# dev-test-proto.net
KiCad netlist of a schematic drawn in EAGLE
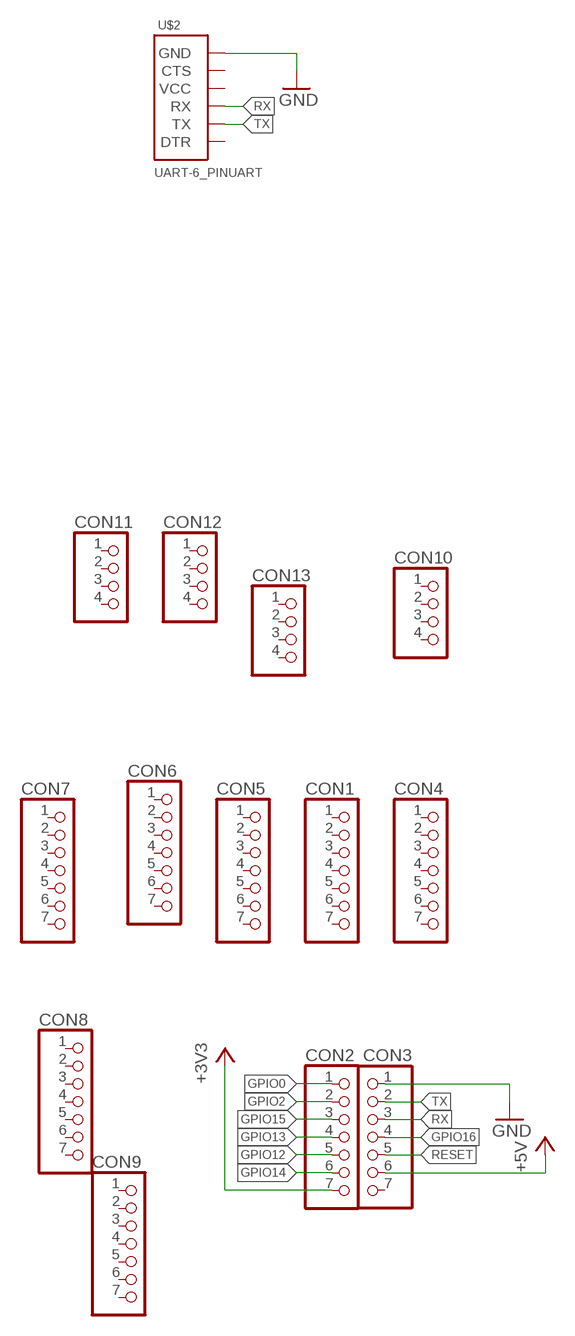
[diagram p0: schematic, sheet 1]

(export (version "E")
  (design (tool "Eeschema 10.0.6"))
  (components
    (comp (ref "CON1")
      (value "GENERIC-1X7THT")
      (footprint "eagle-import:PINHEADER-100MIL-1X7")
      (libsource (lib "eagle-import") (part "GENERIC-1X7THT"))
    )
    (comp (ref "CON2")
      (value "GENERIC-1X7THT")
      (footprint "eagle-import:PINHEADER-100MIL-1X7")
      (libsource (lib "eagle-import") (part "GENERIC-1X7THT"))
    )
    (comp (ref "CON3")
      (value "GENERIC-1X7THT")
      (footprint "eagle-import:PINHEADER-100MIL-1X7")
      (libsource (lib "eagle-import") (part "GENERIC-1X7THT"))
    )
    (comp (ref "CON4")
      (value "GENERIC-1X7THT")
      (footprint "eagle-import:PINHEADER-100MIL-1X7")
      (libsource (lib "eagle-import") (part "GENERIC-1X7THT"))
    )
    (comp (ref "CON5")
      (value "GENERIC-1X7THT")
      (footprint "eagle-import:PINHEADER-100MIL-1X7")
      (libsource (lib "eagle-import") (part "GENERIC-1X7THT"))
    )
    (comp (ref "CON6")
      (value "GENERIC-1X7THT")
      (footprint "eagle-import:PINHEADER-100MIL-1X7")
      (libsource (lib "eagle-import") (part "GENERIC-1X7THT"))
    )
    (comp (ref "CON7")
      (value "GENERIC-1X7THT")
      (footprint "eagle-import:PINHEADER-100MIL-1X7")
      (libsource (lib "eagle-import") (part "GENERIC-1X7THT"))
    )
    (comp (ref "CON8")
      (value "GENERIC-1X7THT")
      (footprint "eagle-import:PINHEADER-100MIL-1X7")
      (libsource (lib "eagle-import") (part "GENERIC-1X7THT"))
    )
    (comp (ref "CON9")
      (value "GENERIC-1X7THT")
      (footprint "eagle-import:PINHEADER-100MIL-1X7")
      (libsource (lib "eagle-import") (part "GENERIC-1X7THT"))
    )
    (comp (ref "CON10")
      (value "GENERIC-1X4STRAIGHT")
      (footprint "eagle-import:PINHEADER-100MIL-1X4-NOSILK")
      (libsource (lib "eagle-import") (part "GENERIC-1X4STRAIGHT"))
    )
    (comp (ref "CON11")
      (value "GENERIC-1X4STRAIGHT")
      (footprint "eagle-import:PINHEADER-100MIL-1X4-NOSILK")
      (libsource (lib "eagle-import") (part "GENERIC-1X4STRAIGHT"))
    )
    (comp (ref "CON12")
      (value "GENERIC-1X4STRAIGHT")
      (footprint "eagle-import:PINHEADER-100MIL-1X4-NOSILK")
      (libsource (lib "eagle-import") (part "GENERIC-1X4STRAIGHT"))
    )
    (comp (ref "CON13")
      (value "GENERIC-1X4STRAIGHT")
      (footprint "eagle-import:PINHEADER-100MIL-1X4-NOSILK")
      (libsource (lib "eagle-import") (part "GENERIC-1X4STRAIGHT"))
    )
    (comp (ref "U$2")
      (value "UART-6_PINUART")
      (footprint "eagle-import:ANGLE-1X6")
      (libsource (lib "eagle-import") (part "UART-6_PINUART"))
    )
  )
  (nets
    (net (code "1") (name "+3V3") (class "Default")
      (node (ref "CON2") (pin "7") (pinfunction "7_7") (pintype "passive"))
    )
    (net (code "2") (name "+5V") (class "Default")
      (node (ref "CON3") (pin "6") (pinfunction "6_6") (pintype "passive"))
    )
    (net (code "3") (name "GND") (class "Default")
      (node (ref "CON3") (pin "1") (pinfunction "1_1") (pintype "passive"))
      (node (ref "U$2") (pin "1") (pinfunction "GND_1") (pintype "bidirectional"))
    )
    (net (code "4") (name "GPIO0") (class "Default")
      (node (ref "CON2") (pin "1") (pinfunction "1_1") (pintype "passive"))
    )
    (net (code "5") (name "GPIO2") (class "Default")
      (node (ref "CON2") (pin "2") (pinfunction "2_2") (pintype "passive"))
    )
    (net (code "6") (name "GPIO12") (class "Default")
      (node (ref "CON2") (pin "5") (pinfunction "5_5") (pintype "passive"))
    )
    (net (code "7") (name "GPIO13") (class "Default")
      (node (ref "CON2") (pin "4") (pinfunction "4_4") (pintype "passive"))
    )
    (net (code "8") (name "GPIO14") (class "Default")
      (node (ref "CON2") (pin "6") (pinfunction "6_6") (pintype "passive"))
    )
    (net (code "9") (name "GPIO15") (class "Default")
      (node (ref "CON2") (pin "3") (pinfunction "3_3") (pintype "passive"))
    )
    (net (code "10") (name "GPIO16") (class "Default")
      (node (ref "CON3") (pin "4") (pinfunction "4_4") (pintype "passive"))
    )
    (net (code "11") (name "RESET") (class "Default")
      (node (ref "CON3") (pin "5") (pinfunction "5_5") (pintype "passive"))
    )
    (net (code "12") (name "RX") (class "Default")
      (node (ref "CON3") (pin "3") (pinfunction "3_3") (pintype "passive"))
      (node (ref "U$2") (pin "4") (pinfunction "RX_4") (pintype "bidirectional"))
    )
    (net (code "13") (name "TX") (class "Default")
      (node (ref "CON3") (pin "2") (pinfunction "2_2") (pintype "passive"))
      (node (ref "U$2") (pin "5") (pinfunction "TX_5") (pintype "bidirectional"))
    )
    (net (code "14") (name "unconnected-(CON1-Pad1)") (class "Default")
      (node (ref "CON1") (pin "1") (pinfunction "1_1") (pintype "passive"))
    )
    (net (code "15") (name "unconnected-(CON1-Pad2)") (class "Default")
      (node (ref "CON1") (pin "2") (pinfunction "2_2") (pintype "passive"))
    )
    (net (code "16") (name "unconnected-(CON1-Pad3)") (class "Default")
      (node (ref "CON1") (pin "3") (pinfunction "3_3") (pintype "passive"))
    )
    (net (code "17") (name "unconnected-(CON1-Pad4)") (class "Default")
      (node (ref "CON1") (pin "4") (pinfunction "4_4") (pintype "passive"))
    )
    (net (code "18") (name "unconnected-(CON1-Pad5)") (class "Default")
      (node (ref "CON1") (pin "5") (pinfunction "5_5") (pintype "passive"))
    )
    (net (code "19") (name "unconnected-(CON1-Pad6)") (class "Default")
      (node (ref "CON1") (pin "6") (pinfunction "6_6") (pintype "passive"))
    )
    (net (code "20") (name "unconnected-(CON1-Pad7)") (class "Default")
      (node (ref "CON1") (pin "7") (pinfunction "7_7") (pintype "passive"))
    )
    (net (code "21") (name "unconnected-(CON3-Pad7)") (class "Default")
      (node (ref "CON3") (pin "7") (pinfunction "7_7") (pintype "passive"))
    )
    (net (code "22") (name "unconnected-(CON4-Pad1)") (class "Default")
      (node (ref "CON4") (pin "1") (pinfunction "1_1") (pintype "passive"))
    )
    (net (code "23") (name "unconnected-(CON4-Pad2)") (class "Default")
      (node (ref "CON4") (pin "2") (pinfunction "2_2") (pintype "passive"))
    )
    (net (code "24") (name "unconnected-(CON4-Pad3)") (class "Default")
      (node (ref "CON4") (pin "3") (pinfunction "3_3") (pintype "passive"))
    )
    (net (code "25") (name "unconnected-(CON4-Pad4)") (class "Default")
      (node (ref "CON4") (pin "4") (pinfunction "4_4") (pintype "passive"))
    )
    (net (code "26") (name "unconnected-(CON4-Pad5)") (class "Default")
      (node (ref "CON4") (pin "5") (pinfunction "5_5") (pintype "passive"))
    )
    (net (code "27") (name "unconnected-(CON4-Pad6)") (class "Default")
      (node (ref "CON4") (pin "6") (pinfunction "6_6") (pintype "passive"))
    )
    (net (code "28") (name "unconnected-(CON4-Pad7)") (class "Default")
      (node (ref "CON4") (pin "7") (pinfunction "7_7") (pintype "passive"))
    )
    (net (code "29") (name "unconnected-(CON5-Pad1)") (class "Default")
      (node (ref "CON5") (pin "1") (pinfunction "1_1") (pintype "passive"))
    )
    (net (code "30") (name "unconnected-(CON5-Pad2)") (class "Default")
      (node (ref "CON5") (pin "2") (pinfunction "2_2") (pintype "passive"))
    )
    (net (code "31") (name "unconnected-(CON5-Pad3)") (class "Default")
      (node (ref "CON5") (pin "3") (pinfunction "3_3") (pintype "passive"))
    )
    (net (code "32") (name "unconnected-(CON5-Pad4)") (class "Default")
      (node (ref "CON5") (pin "4") (pinfunction "4_4") (pintype "passive"))
    )
    (net (code "33") (name "unconnected-(CON5-Pad5)") (class "Default")
      (node (ref "CON5") (pin "5") (pinfunction "5_5") (pintype "passive"))
    )
    (net (code "34") (name "unconnected-(CON5-Pad6)") (class "Default")
      (node (ref "CON5") (pin "6") (pinfunction "6_6") (pintype "passive"))
    )
    (net (code "35") (name "unconnected-(CON5-Pad7)") (class "Default")
      (node (ref "CON5") (pin "7") (pinfunction "7_7") (pintype "passive"))
    )
    (net (code "36") (name "unconnected-(CON6-Pad1)") (class "Default")
      (node (ref "CON6") (pin "1") (pinfunction "1_1") (pintype "passive"))
    )
    (net (code "37") (name "unconnected-(CON6-Pad2)") (class "Default")
      (node (ref "CON6") (pin "2") (pinfunction "2_2") (pintype "passive"))
    )
    (net (code "38") (name "unconnected-(CON6-Pad3)") (class "Default")
      (node (ref "CON6") (pin "3") (pinfunction "3_3") (pintype "passive"))
    )
    (net (code "39") (name "unconnected-(CON6-Pad4)") (class "Default")
      (node (ref "CON6") (pin "4") (pinfunction "4_4") (pintype "passive"))
    )
    (net (code "40") (name "unconnected-(CON6-Pad5)") (class "Default")
      (node (ref "CON6") (pin "5") (pinfunction "5_5") (pintype "passive"))
    )
    (net (code "41") (name "unconnected-(CON6-Pad6)") (class "Default")
      (node (ref "CON6") (pin "6") (pinfunction "6_6") (pintype "passive"))
    )
    (net (code "42") (name "unconnected-(CON6-Pad7)") (class "Default")
      (node (ref "CON6") (pin "7") (pinfunction "7_7") (pintype "passive"))
    )
    (net (code "43") (name "unconnected-(CON7-Pad1)") (class "Default")
      (node (ref "CON7") (pin "1") (pinfunction "1_1") (pintype "passive"))
    )
    (net (code "44") (name "unconnected-(CON7-Pad2)") (class "Default")
      (node (ref "CON7") (pin "2") (pinfunction "2_2") (pintype "passive"))
    )
    (net (code "45") (name "unconnected-(CON7-Pad3)") (class "Default")
      (node (ref "CON7") (pin "3") (pinfunction "3_3") (pintype "passive"))
    )
    (net (code "46") (name "unconnected-(CON7-Pad4)") (class "Default")
      (node (ref "CON7") (pin "4") (pinfunction "4_4") (pintype "passive"))
    )
    (net (code "47") (name "unconnected-(CON7-Pad5)") (class "Default")
      (node (ref "CON7") (pin "5") (pinfunction "5_5") (pintype "passive"))
    )
    (net (code "48") (name "unconnected-(CON7-Pad6)") (class "Default")
      (node (ref "CON7") (pin "6") (pinfunction "6_6") (pintype "passive"))
    )
    (net (code "49") (name "unconnected-(CON7-Pad7)") (class "Default")
      (node (ref "CON7") (pin "7") (pinfunction "7_7") (pintype "passive"))
    )
    (net (code "50") (name "unconnected-(CON8-Pad1)") (class "Default")
      (node (ref "CON8") (pin "1") (pinfunction "1_1") (pintype "passive"))
    )
    (net (code "51") (name "unconnected-(CON8-Pad2)") (class "Default")
      (node (ref "CON8") (pin "2") (pinfunction "2_2") (pintype "passive"))
    )
    (net (code "52") (name "unconnected-(CON8-Pad3)") (class "Default")
      (node (ref "CON8") (pin "3") (pinfunction "3_3") (pintype "passive"))
    )
    (net (code "53") (name "unconnected-(CON8-Pad4)") (class "Default")
      (node (ref "CON8") (pin "4") (pinfunction "4_4") (pintype "passive"))
    )
    (net (code "54") (name "unconnected-(CON8-Pad5)") (class "Default")
      (node (ref "CON8") (pin "5") (pinfunction "5_5") (pintype "passive"))
    )
    (net (code "55") (name "unconnected-(CON8-Pad6)") (class "Default")
      (node (ref "CON8") (pin "6") (pinfunction "6_6") (pintype "passive"))
    )
    (net (code "56") (name "unconnected-(CON8-Pad7)") (class "Default")
      (node (ref "CON8") (pin "7") (pinfunction "7_7") (pintype "passive"))
    )
    (net (code "57") (name "unconnected-(CON9-Pad1)") (class "Default")
      (node (ref "CON9") (pin "1") (pinfunction "1_1") (pintype "passive"))
    )
    (net (code "58") (name "unconnected-(CON9-Pad2)") (class "Default")
      (node (ref "CON9") (pin "2") (pinfunction "2_2") (pintype "passive"))
    )
    (net (code "59") (name "unconnected-(CON9-Pad3)") (class "Default")
      (node (ref "CON9") (pin "3") (pinfunction "3_3") (pintype "passive"))
    )
    (net (code "60") (name "unconnected-(CON9-Pad4)") (class "Default")
      (node (ref "CON9") (pin "4") (pinfunction "4_4") (pintype "passive"))
    )
    (net (code "61") (name "unconnected-(CON9-Pad5)") (class "Default")
      (node (ref "CON9") (pin "5") (pinfunction "5_5") (pintype "passive"))
    )
    (net (code "62") (name "unconnected-(CON9-Pad6)") (class "Default")
      (node (ref "CON9") (pin "6") (pinfunction "6_6") (pintype "passive"))
    )
    (net (code "63") (name "unconnected-(CON9-Pad7)") (class "Default")
      (node (ref "CON9") (pin "7") (pinfunction "7_7") (pintype "passive"))
    )
    (net (code "64") (name "unconnected-(CON10-Pad1)") (class "Default")
      (node (ref "CON10") (pin "1") (pinfunction "1_1") (pintype "passive"))
    )
    (net (code "65") (name "unconnected-(CON10-Pad2)") (class "Default")
      (node (ref "CON10") (pin "2") (pinfunction "2_2") (pintype "passive"))
    )
    (net (code "66") (name "unconnected-(CON10-Pad3)") (class "Default")
      (node (ref "CON10") (pin "3") (pinfunction "3_3") (pintype "passive"))
    )
    (net (code "67") (name "unconnected-(CON10-Pad4)") (class "Default")
      (node (ref "CON10") (pin "4") (pinfunction "4_4") (pintype "passive"))
    )
    (net (code "68") (name "unconnected-(CON11-Pad1)") (class "Default")
      (node (ref "CON11") (pin "1") (pinfunction "1_1") (pintype "passive"))
    )
    (net (code "69") (name "unconnected-(CON11-Pad2)") (class "Default")
      (node (ref "CON11") (pin "2") (pinfunction "2_2") (pintype "passive"))
    )
    (net (code "70") (name "unconnected-(CON11-Pad3)") (class "Default")
      (node (ref "CON11") (pin "3") (pinfunction "3_3") (pintype "passive"))
    )
    (net (code "71") (name "unconnected-(CON11-Pad4)") (class "Default")
      (node (ref "CON11") (pin "4") (pinfunction "4_4") (pintype "passive"))
    )
    (net (code "72") (name "unconnected-(CON12-Pad1)") (class "Default")
      (node (ref "CON12") (pin "1") (pinfunction "1_1") (pintype "passive"))
    )
    (net (code "73") (name "unconnected-(CON12-Pad2)") (class "Default")
      (node (ref "CON12") (pin "2") (pinfunction "2_2") (pintype "passive"))
    )
    (net (code "74") (name "unconnected-(CON12-Pad3)") (class "Default")
      (node (ref "CON12") (pin "3") (pinfunction "3_3") (pintype "passive"))
    )
    (net (code "75") (name "unconnected-(CON12-Pad4)") (class "Default")
      (node (ref "CON12") (pin "4") (pinfunction "4_4") (pintype "passive"))
    )
    (net (code "76") (name "unconnected-(CON13-Pad1)") (class "Default")
      (node (ref "CON13") (pin "1") (pinfunction "1_1") (pintype "passive"))
    )
    (net (code "77") (name "unconnected-(CON13-Pad2)") (class "Default")
      (node (ref "CON13") (pin "2") (pinfunction "2_2") (pintype "passive"))
    )
    (net (code "78") (name "unconnected-(CON13-Pad3)") (class "Default")
      (node (ref "CON13") (pin "3") (pinfunction "3_3") (pintype "passive"))
    )
    (net (code "79") (name "unconnected-(CON13-Pad4)") (class "Default")
      (node (ref "CON13") (pin "4") (pinfunction "4_4") (pintype "passive"))
    )
    (net (code "80") (name "unconnected-(U$2-CTS-Pad2)") (class "Default")
      (node (ref "U$2") (pin "2") (pinfunction "CTS_2") (pintype "bidirectional"))
    )
    (net (code "81") (name "unconnected-(U$2-DTR-Pad6)") (class "Default")
      (node (ref "U$2") (pin "6") (pinfunction "DTR_6") (pintype "bidirectional"))
    )
    (net (code "82") (name "unconnected-(U$2-VCC-Pad3)") (class "Default")
      (node (ref "U$2") (pin "3") (pinfunction "VCC_3") (pintype "bidirectional"))
    )
  )
)
